# openSX70-dongle_v5-1-dual-led.net
KiCad netlist of a schematic drawn in EAGLE
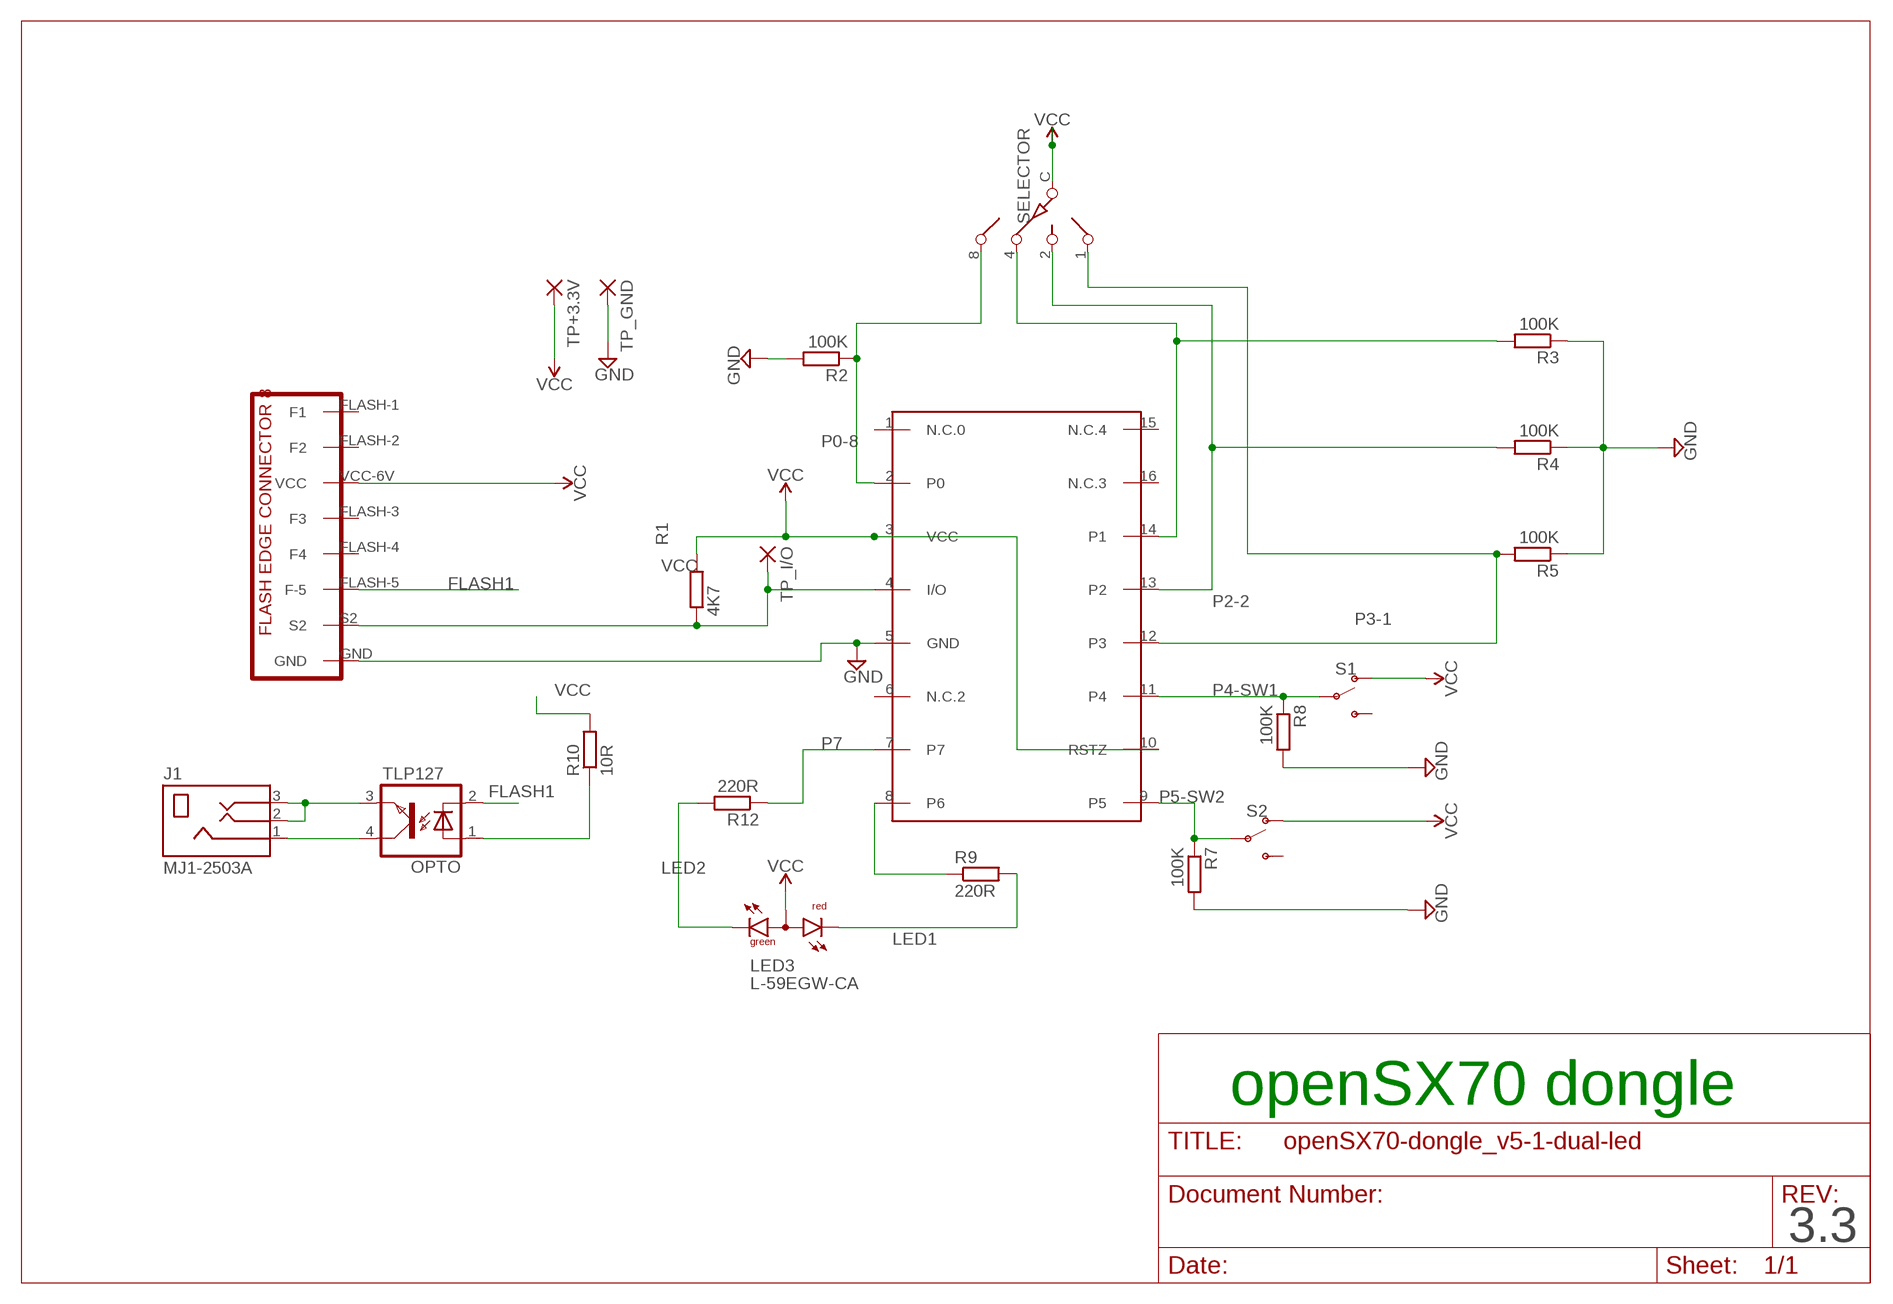
[diagram p0: schematic, sheet 1]

(export (version "E")
  (design (tool "Eeschema 10.0.6"))
  (components
    (comp (ref "DS2408")
      (value "DS2408")
      (footprint "eagle-import:SO16")
      (libsource (lib "eagle-import") (part "DS2408"))
    )
    (comp (ref "J1")
      (value "MJ1-2503A")
      (footprint "eagle-import:CUI_MJ1-2503A")
      (fields (field (name "DIGI-KEY_PART_NUMBER") "CP1-2503AM-ND") (field (name "MF") "CUI Inc."))
      (libsource (lib "eagle-import") (part "MJ1-2503A"))
    )
    (comp (ref "LED3")
      (value "L-59EGW-CA")
      (footprint "eagle-import:L-59EGW-CA")
      (libsource (lib "eagle-import") (part "L-59EGW-CA"))
    )
    (comp (ref "OPTO")
      (value "TLP127")
      (footprint "eagle-import:SO-4")
      (libsource (lib "eagle-import") (part "TLP127"))
    )
    (comp (ref "R1")
      (value "4K7")
      (footprint "eagle-import:R0603")
      (libsource (lib "eagle-import") (part "R-EU_R0603"))
    )
    (comp (ref "R2")
      (value "100K")
      (footprint "eagle-import:R0603")
      (libsource (lib "eagle-import") (part "R-EU_R0603"))
    )
    (comp (ref "R3")
      (value "100K")
      (footprint "eagle-import:R0603")
      (libsource (lib "eagle-import") (part "R-EU_R0603"))
    )
    (comp (ref "R4")
      (value "100K")
      (footprint "eagle-import:R0603")
      (libsource (lib "eagle-import") (part "R-EU_R0603"))
    )
    (comp (ref "R5")
      (value "100K")
      (footprint "eagle-import:R0603")
      (libsource (lib "eagle-import") (part "R-EU_R0603"))
    )
    (comp (ref "R7")
      (value "100K")
      (footprint "eagle-import:R0603")
      (libsource (lib "eagle-import") (part "R-EU_R0603"))
    )
    (comp (ref "R8")
      (value "100K")
      (footprint "eagle-import:R0603")
      (libsource (lib "eagle-import") (part "R-EU_R0603"))
    )
    (comp (ref "R9")
      (value "220R")
      (footprint "eagle-import:R0603")
      (libsource (lib "eagle-import") (part "R-EU_R0603"))
    )
    (comp (ref "R10")
      (value "10R")
      (footprint "eagle-import:R0603")
      (libsource (lib "eagle-import") (part "resistor_348_R-EU_R0603"))
    )
    (comp (ref "R12")
      (value "220R")
      (footprint "eagle-import:R0603")
      (libsource (lib "eagle-import") (part "R-EU_R0603"))
    )
    (comp (ref "S1")
      (value "SWITCH-SPDT-SMD-RIGHT-ANGLE")
      (footprint "eagle-import:SWITCH_SPST_SMD_A")
      (libsource (lib "eagle-import") (part "SWITCH-SPDT-SMD-RIGHT-ANGLE"))
    )
    (comp (ref "S2")
      (value "SWITCH-SPDT-SMD-RIGHT-ANGLE")
      (footprint "eagle-import:SWITCH_SPST_SMD_A")
      (libsource (lib "eagle-import") (part "SWITCH-SPDT-SMD-RIGHT-ANGLE"))
    )
    (comp (ref "SELECTOR")
      (value "SW-C16")
      (footprint "eagle-import:SW-C16")
      (libsource (lib "eagle-import") (part "SW-C16"))
    )
    (comp (ref "TP+3.3V")
      (value "SMD2")
      (footprint "eagle-import:SMD1,27-2,54")
      (libsource (lib "eagle-import") (part "SMD2"))
    )
    (comp (ref "TP_GND")
      (value "SMD2")
      (footprint "eagle-import:SMD1,27-2,54")
      (libsource (lib "eagle-import") (part "SMD2"))
    )
    (comp (ref "TP_I/O")
      (value "SMD2")
      (footprint "eagle-import:SMD1,27-2,54")
      (libsource (lib "eagle-import") (part "SMD2"))
    )
    (comp (ref "U$2")
      (value "SX70-FLASH-EDGE8-MALE-PROPER")
      (footprint "eagle-import:SX70-FLASH-EDGE8")
      (libsource (lib "eagle-import") (part "SX70-FLASH-EDGE8-MALE-PROPER"))
    )
  )
  (nets
    (net (code "1") (name "/FLASH1") (class "Default")
      (node (ref "OPTO") (pin "2") (pinfunction "C_2") (pintype "passive"))
      (node (ref "U$2") (pin "FLASH-5") (pinfunction "F-5_FLASH-5") (pintype "bidirectional"))
    )
    (net (code "2") (name "/LED1") (class "Default")
      (node (ref "LED3") (pin "1") (pinfunction "CR_1") (pintype "passive"))
      (node (ref "R9") (pin "2") (pinfunction "2_2") (pintype "passive"))
    )
    (net (code "3") (name "/LED2") (class "Default")
      (node (ref "LED3") (pin "3") (pinfunction "CG_3") (pintype "passive"))
      (node (ref "R12") (pin "2") (pinfunction "2_2") (pintype "passive"))
    )
    (net (code "4") (name "/P0-8") (class "Default")
      (node (ref "DS2408") (pin "2") (pinfunction "P0_2") (pintype "bidirectional"))
      (node (ref "R2") (pin "1") (pinfunction "1_1") (pintype "passive"))
      (node (ref "SELECTOR") (pin "8") (pinfunction "8_8") (pintype "passive"))
    )
    (net (code "5") (name "/P2-2") (class "Default")
      (node (ref "DS2408") (pin "13") (pinfunction "P2_13") (pintype "bidirectional"))
      (node (ref "R4") (pin "2") (pinfunction "2_2") (pintype "passive"))
      (node (ref "SELECTOR") (pin "2") (pinfunction "2_2") (pintype "passive"))
    )
    (net (code "6") (name "/P3-1") (class "Default")
      (node (ref "DS2408") (pin "12") (pinfunction "P3_12") (pintype "bidirectional"))
      (node (ref "R5") (pin "2") (pinfunction "2_2") (pintype "passive"))
      (node (ref "SELECTOR") (pin "1") (pinfunction "1_1") (pintype "passive"))
    )
    (net (code "7") (name "/P4-SW1") (class "Default")
      (node (ref "DS2408") (pin "11") (pinfunction "P4_11") (pintype "bidirectional"))
      (node (ref "R8") (pin "1") (pinfunction "1_1") (pintype "passive"))
      (node (ref "S1") (pin "2") (pinfunction "P_2") (pintype "passive"))
    )
    (net (code "8") (name "/P5-SW2") (class "Default")
      (node (ref "DS2408") (pin "9") (pinfunction "P5_9") (pintype "bidirectional"))
      (node (ref "R7") (pin "1") (pinfunction "1_1") (pintype "passive"))
      (node (ref "S2") (pin "2") (pinfunction "P_2") (pintype "passive"))
    )
    (net (code "9") (name "/P7") (class "Default")
      (node (ref "DS2408") (pin "7") (pinfunction "P7_7") (pintype "bidirectional"))
      (node (ref "R12") (pin "1") (pinfunction "1_1") (pintype "passive"))
    )
    (net (code "10") (name "GND") (class "Default")
      (node (ref "DS2408") (pin "5") (pinfunction "GND_5") (pintype "bidirectional"))
      (node (ref "R2") (pin "2") (pinfunction "2_2") (pintype "passive"))
      (node (ref "R3") (pin "1") (pinfunction "1_1") (pintype "passive"))
      (node (ref "R4") (pin "1") (pinfunction "1_1") (pintype "passive"))
      (node (ref "R5") (pin "1") (pinfunction "1_1") (pintype "passive"))
      (node (ref "R7") (pin "2") (pinfunction "2_2") (pintype "passive"))
      (node (ref "R8") (pin "2") (pinfunction "2_2") (pintype "passive"))
      (node (ref "TP_GND") (pin "1") (pinfunction "P_1") (pintype "passive"))
      (node (ref "U$2") (pin "GND") (pinfunction "GND_GND") (pintype "bidirectional"))
    )
    (net (code "11") (name "Net-(DS2408-I{slash}O)") (class "Default")
      (node (ref "DS2408") (pin "4") (pinfunction "I/O_4") (pintype "bidirectional"))
      (node (ref "R1") (pin "1") (pinfunction "1_1") (pintype "passive"))
      (node (ref "TP_I/O") (pin "1") (pinfunction "P_1") (pintype "passive"))
      (node (ref "U$2") (pin "S2") (pinfunction "S2_S2") (pintype "bidirectional"))
    )
    (net (code "12") (name "Net-(DS2408-P1)") (class "Default")
      (node (ref "DS2408") (pin "14") (pinfunction "P1_14") (pintype "bidirectional"))
      (node (ref "R3") (pin "2") (pinfunction "2_2") (pintype "passive"))
      (node (ref "SELECTOR") (pin "4") (pinfunction "4_4") (pintype "passive"))
    )
    (net (code "13") (name "Net-(DS2408-P6)") (class "Default")
      (node (ref "DS2408") (pin "8") (pinfunction "P6_8") (pintype "bidirectional"))
      (node (ref "R9") (pin "1") (pinfunction "1_1") (pintype "passive"))
    )
    (net (code "14") (name "Net-(OPTO-A)") (class "Default")
      (node (ref "OPTO") (pin "1") (pinfunction "A_1") (pintype "passive"))
      (node (ref "R10") (pin "1") (pinfunction "1_1") (pintype "passive"))
    )
    (net (code "15") (name "Net-(OPTO-COL)") (class "Default")
      (node (ref "J1") (pin "1") (pinfunction "1_1") (pintype "passive"))
      (node (ref "OPTO") (pin "4") (pinfunction "COL_4") (pintype "passive"))
    )
    (net (code "16") (name "Net-(OPTO-EMIT)") (class "Default")
      (node (ref "J1") (pin "2") (pinfunction "2_2") (pintype "passive"))
      (node (ref "J1") (pin "3") (pinfunction "3_3") (pintype "passive"))
      (node (ref "OPTO") (pin "3") (pinfunction "EMIT_3") (pintype "passive"))
    )
    (net (code "17") (name "VCC") (class "Default")
      (node (ref "DS2408") (pin "10") (pinfunction "RSTZ_10") (pintype "bidirectional"))
      (node (ref "DS2408") (pin "3") (pinfunction "VCC_3") (pintype "bidirectional"))
      (node (ref "LED3") (pin "2") (pinfunction "A_2") (pintype "passive"))
      (node (ref "R1") (pin "2") (pinfunction "2_2") (pintype "passive"))
      (node (ref "R10") (pin "2") (pinfunction "2_2") (pintype "passive"))
      (node (ref "S1") (pin "1") (pinfunction "O_1") (pintype "passive"))
      (node (ref "S2") (pin "1") (pinfunction "O_1") (pintype "passive"))
      (node (ref "SELECTOR") (pin "C") (pinfunction "C_C") (pintype "passive"))
      (node (ref "TP+3.3V") (pin "1") (pinfunction "P_1") (pintype "passive"))
      (node (ref "U$2") (pin "VCC-6V") (pinfunction "VCC_VCC-6V") (pintype "bidirectional"))
    )
    (net (code "18") (name "unconnected-(DS2408-N.C.0-Pad1)") (class "Default")
      (node (ref "DS2408") (pin "1") (pinfunction "N.C.0_1") (pintype "bidirectional"))
    )
    (net (code "19") (name "unconnected-(DS2408-N.C.2-Pad6)") (class "Default")
      (node (ref "DS2408") (pin "6") (pinfunction "N.C.2_6") (pintype "bidirectional"))
    )
    (net (code "20") (name "unconnected-(DS2408-N.C.3-Pad16)") (class "Default")
      (node (ref "DS2408") (pin "16") (pinfunction "N.C.3_16") (pintype "bidirectional"))
    )
    (net (code "21") (name "unconnected-(DS2408-N.C.4-Pad15)") (class "Default")
      (node (ref "DS2408") (pin "15") (pinfunction "N.C.4_15") (pintype "bidirectional"))
    )
    (net (code "22") (name "unconnected-(S1-S-Pad3)") (class "Default")
      (node (ref "S1") (pin "3") (pinfunction "S_3") (pintype "passive"))
    )
    (net (code "23") (name "unconnected-(S2-S-Pad3)") (class "Default")
      (node (ref "S2") (pin "3") (pinfunction "S_3") (pintype "passive"))
    )
    (net (code "24") (name "unconnected-(U$2-F1-PadFLASH-1)") (class "Default")
      (node (ref "U$2") (pin "FLASH-1") (pinfunction "F1_FLASH-1") (pintype "bidirectional"))
    )
    (net (code "25") (name "unconnected-(U$2-F2-PadFLASH-2)") (class "Default")
      (node (ref "U$2") (pin "FLASH-2") (pinfunction "F2_FLASH-2") (pintype "bidirectional"))
    )
    (net (code "26") (name "unconnected-(U$2-F3-PadFLASH-3)") (class "Default")
      (node (ref "U$2") (pin "FLASH-3") (pinfunction "F3_FLASH-3") (pintype "bidirectional"))
    )
    (net (code "27") (name "unconnected-(U$2-F4-PadFLASH-4)") (class "Default")
      (node (ref "U$2") (pin "FLASH-4") (pinfunction "F4_FLASH-4") (pintype "bidirectional"))
    )
  )
)
